# J4-B64_B65.net
KiCad netlist of a schematic drawn in Altium Designer
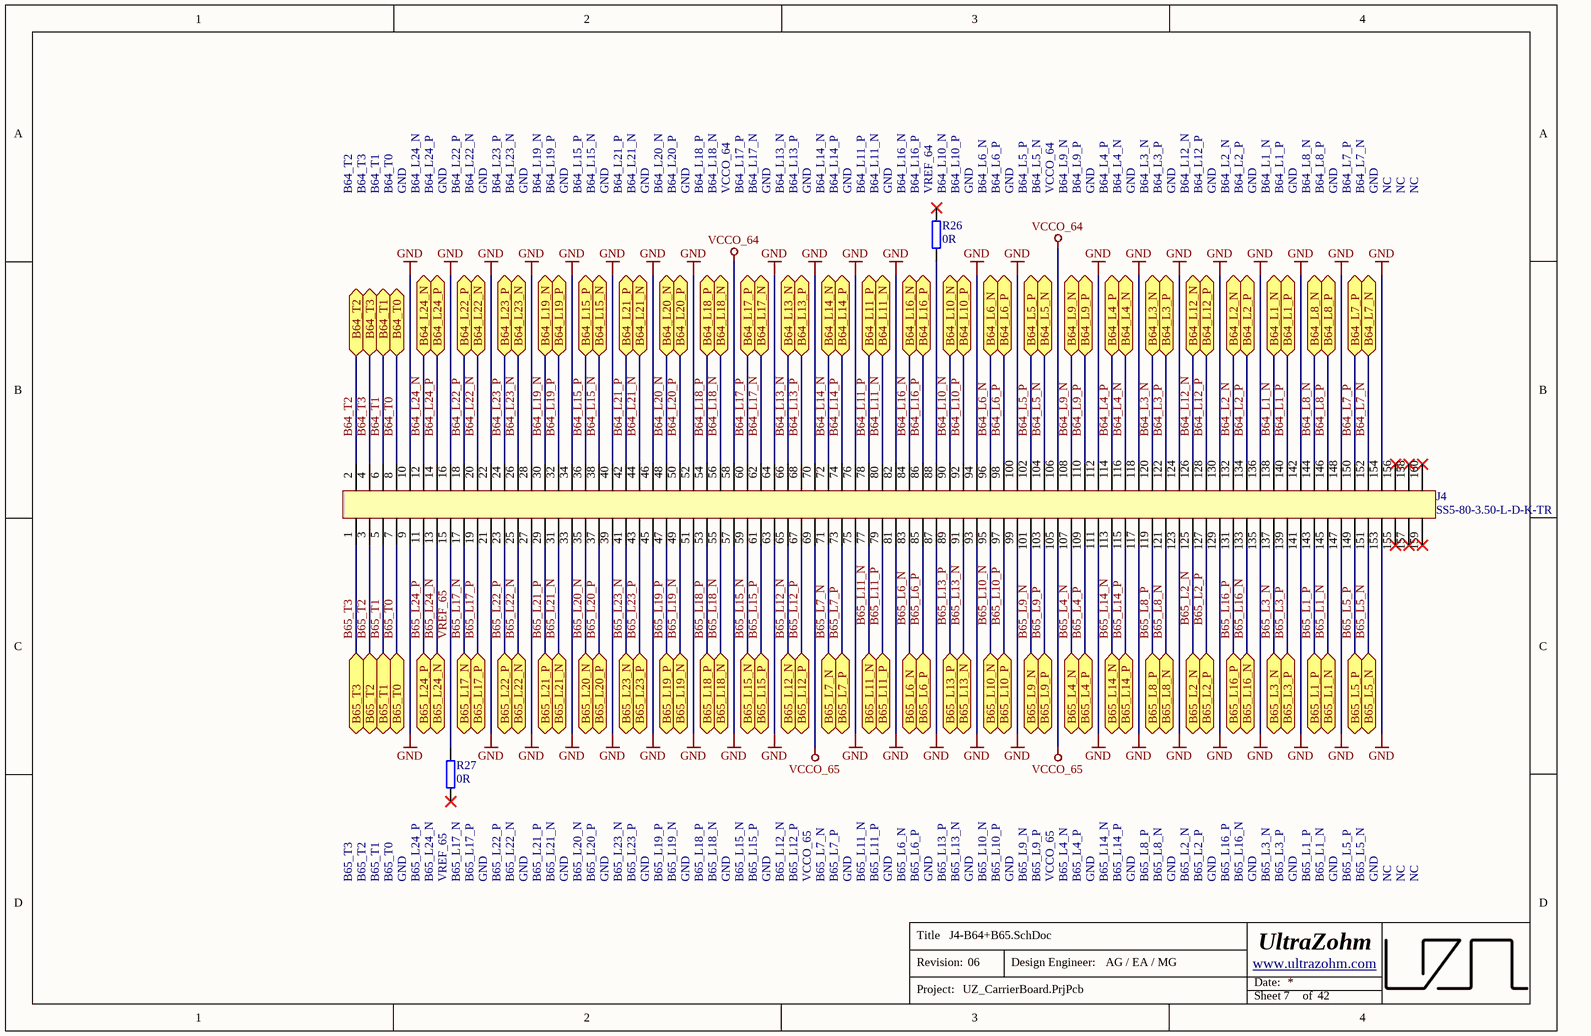
[diagram p0: J4-B64+B65.SchDoc]

(export (version "E")
  (design (tool "Eeschema 10.0.6"))
  (components
    (comp (ref "J4")
      (value "SS5-80-3.50-L-D-K-TR")
      (footprint "SS5-80-3.50-L-D-K-TR")
      (description "0.5 mm Ultra Fine Pitch Socket REF192552-01, 160 Pins")
      (fields
        (field (name "MANUFACTURER") "SAMTEC")
        (field (name "LCSC PART NUMBER") "C5292077")
        (field (name "CREATED FROM") "MGremer")
      )
      (libsource (lib "user") (part "SS5-80-3.50-L-D-K-TR"))
    )
    (comp (ref "R26")
      (value "0R")
      (footprint "R_0603_TE")
      (description "Generic resistor")
      (fields
        (field (name "TOLERANCE") "1 %")
        (field (name "MANUFACTURER PART NUMBER") "UZgen_R_0603_0R")
        (field (name "CREATED FROM") "UZgenTool")
      )
      (libsource (lib "user") (part "RES"))
    )
    (comp (ref "R27")
      (value "0R")
      (footprint "R_0603_TE")
      (description "Generic resistor")
      (fields
        (field (name "TOLERANCE") "1 %")
        (field (name "MANUFACTURER PART NUMBER") "UZgen_R_0603_0R")
        (field (name "CREATED FROM") "UZgenTool")
      )
      (libsource (lib "user") (part "RES"))
    )
  )
  (nets
    (net (code "1") (name "/B64_L1_N") (class "Default")
      (node (ref "J4") (pin "138") (pinfunction "138_138") (pintype "passive"))
    )
    (net (code "2") (name "/B64_L1_P") (class "Default")
      (node (ref "J4") (pin "140") (pinfunction "140_140") (pintype "passive"))
    )
    (net (code "3") (name "/B64_L2_N") (class "Default")
      (node (ref "J4") (pin "132") (pinfunction "132_132") (pintype "passive"))
    )
    (net (code "4") (name "/B64_L2_P") (class "Default")
      (node (ref "J4") (pin "134") (pinfunction "134_134") (pintype "passive"))
    )
    (net (code "5") (name "/B64_L3_N") (class "Default")
      (node (ref "J4") (pin "120") (pinfunction "120_120") (pintype "passive"))
    )
    (net (code "6") (name "/B64_L3_P") (class "Default")
      (node (ref "J4") (pin "122") (pinfunction "122_122") (pintype "passive"))
    )
    (net (code "7") (name "/B64_L4_N") (class "Default")
      (node (ref "J4") (pin "116") (pinfunction "116_116") (pintype "passive"))
    )
    (net (code "8") (name "/B64_L4_P") (class "Default")
      (node (ref "J4") (pin "114") (pinfunction "114_114") (pintype "passive"))
    )
    (net (code "9") (name "/B64_L5_N") (class "Default")
      (node (ref "J4") (pin "104") (pinfunction "104_104") (pintype "passive"))
    )
    (net (code "10") (name "/B64_L5_P") (class "Default")
      (node (ref "J4") (pin "102") (pinfunction "102_102") (pintype "passive"))
    )
    (net (code "11") (name "/B64_L6_N") (class "Default")
      (node (ref "J4") (pin "96") (pinfunction "96_96") (pintype "passive"))
    )
    (net (code "12") (name "/B64_L6_P") (class "Default")
      (node (ref "J4") (pin "98") (pinfunction "98_98") (pintype "passive"))
    )
    (net (code "13") (name "/B64_L7_N") (class "Default")
      (node (ref "J4") (pin "152") (pinfunction "152_152") (pintype "passive"))
    )
    (net (code "14") (name "/B64_L7_P") (class "Default")
      (node (ref "J4") (pin "150") (pinfunction "150_150") (pintype "passive"))
    )
    (net (code "15") (name "/B64_L8_N") (class "Default")
      (node (ref "J4") (pin "144") (pinfunction "144_144") (pintype "passive"))
    )
    (net (code "16") (name "/B64_L8_P") (class "Default")
      (node (ref "J4") (pin "146") (pinfunction "146_146") (pintype "passive"))
    )
    (net (code "17") (name "/B64_L9_N") (class "Default")
      (node (ref "J4") (pin "108") (pinfunction "108_108") (pintype "passive"))
    )
    (net (code "18") (name "/B64_L9_P") (class "Default")
      (node (ref "J4") (pin "110") (pinfunction "110_110") (pintype "passive"))
    )
    (net (code "19") (name "/B64_L10_N") (class "Default")
      (node (ref "J4") (pin "90") (pinfunction "90_90") (pintype "passive"))
    )
    (net (code "20") (name "/B64_L10_P") (class "Default")
      (node (ref "J4") (pin "92") (pinfunction "92_92") (pintype "passive"))
    )
    (net (code "21") (name "/B64_L11_N") (class "Default")
      (node (ref "J4") (pin "80") (pinfunction "80_80") (pintype "passive"))
    )
    (net (code "22") (name "/B64_L11_P") (class "Default")
      (node (ref "J4") (pin "78") (pinfunction "78_78") (pintype "passive"))
    )
    (net (code "23") (name "/B64_L12_N") (class "Default")
      (node (ref "J4") (pin "126") (pinfunction "126_126") (pintype "passive"))
    )
    (net (code "24") (name "/B64_L12_P") (class "Default")
      (node (ref "J4") (pin "128") (pinfunction "128_128") (pintype "passive"))
    )
    (net (code "25") (name "/B64_L13_N") (class "Default")
      (node (ref "J4") (pin "66") (pinfunction "66_66") (pintype "passive"))
    )
    (net (code "26") (name "/B64_L13_P") (class "Default")
      (node (ref "J4") (pin "68") (pinfunction "68_68") (pintype "passive"))
    )
    (net (code "27") (name "/B64_L14_N") (class "Default")
      (node (ref "J4") (pin "72") (pinfunction "72_72") (pintype "passive"))
    )
    (net (code "28") (name "/B64_L14_P") (class "Default")
      (node (ref "J4") (pin "74") (pinfunction "74_74") (pintype "passive"))
    )
    (net (code "29") (name "/B64_L15_N") (class "Default")
      (node (ref "J4") (pin "38") (pinfunction "38_38") (pintype "passive"))
    )
    (net (code "30") (name "/B64_L15_P") (class "Default")
      (node (ref "J4") (pin "36") (pinfunction "36_36") (pintype "passive"))
    )
    (net (code "31") (name "/B64_L16_N") (class "Default")
      (node (ref "J4") (pin "84") (pinfunction "84_84") (pintype "passive"))
    )
    (net (code "32") (name "/B64_L16_P") (class "Default")
      (node (ref "J4") (pin "86") (pinfunction "86_86") (pintype "passive"))
    )
    (net (code "33") (name "/B64_L17_N") (class "Default")
      (node (ref "J4") (pin "62") (pinfunction "62_62") (pintype "passive"))
    )
    (net (code "34") (name "/B64_L17_P") (class "Default")
      (node (ref "J4") (pin "60") (pinfunction "60_60") (pintype "passive"))
    )
    (net (code "35") (name "/B64_L18_N") (class "Default")
      (node (ref "J4") (pin "56") (pinfunction "56_56") (pintype "passive"))
    )
    (net (code "36") (name "/B64_L18_P") (class "Default")
      (node (ref "J4") (pin "54") (pinfunction "54_54") (pintype "passive"))
    )
    (net (code "37") (name "/B64_L19_N") (class "Default")
      (node (ref "J4") (pin "30") (pinfunction "30_30") (pintype "passive"))
    )
    (net (code "38") (name "/B64_L19_P") (class "Default")
      (node (ref "J4") (pin "32") (pinfunction "32_32") (pintype "passive"))
    )
    (net (code "39") (name "/B64_L20_N") (class "Default")
      (node (ref "J4") (pin "48") (pinfunction "48_48") (pintype "passive"))
    )
    (net (code "40") (name "/B64_L20_P") (class "Default")
      (node (ref "J4") (pin "50") (pinfunction "50_50") (pintype "passive"))
    )
    (net (code "41") (name "/B64_L21_N") (class "Default")
      (node (ref "J4") (pin "44") (pinfunction "44_44") (pintype "passive"))
    )
    (net (code "42") (name "/B64_L21_P") (class "Default")
      (node (ref "J4") (pin "42") (pinfunction "42_42") (pintype "passive"))
    )
    (net (code "43") (name "/B64_L22_N") (class "Default")
      (node (ref "J4") (pin "20") (pinfunction "20_20") (pintype "passive"))
    )
    (net (code "44") (name "/B64_L22_P") (class "Default")
      (node (ref "J4") (pin "18") (pinfunction "18_18") (pintype "passive"))
    )
    (net (code "45") (name "/B64_L23_N") (class "Default")
      (node (ref "J4") (pin "26") (pinfunction "26_26") (pintype "passive"))
    )
    (net (code "46") (name "/B64_L23_P") (class "Default")
      (node (ref "J4") (pin "24") (pinfunction "24_24") (pintype "passive"))
    )
    (net (code "47") (name "/B64_L24_N") (class "Default")
      (node (ref "J4") (pin "12") (pinfunction "12_12") (pintype "passive"))
    )
    (net (code "48") (name "/B64_L24_P") (class "Default")
      (node (ref "J4") (pin "14") (pinfunction "14_14") (pintype "passive"))
    )
    (net (code "49") (name "/B64_T0") (class "Default")
      (node (ref "J4") (pin "8") (pinfunction "8_8") (pintype "passive"))
    )
    (net (code "50") (name "/B64_T1") (class "Default")
      (node (ref "J4") (pin "6") (pinfunction "6_6") (pintype "passive"))
    )
    (net (code "51") (name "/B64_T2") (class "Default")
      (node (ref "J4") (pin "2") (pinfunction "2_2") (pintype "passive"))
    )
    (net (code "52") (name "/B64_T3") (class "Default")
      (node (ref "J4") (pin "4") (pinfunction "4_4") (pintype "passive"))
    )
    (net (code "53") (name "/B65_L1_N") (class "Default")
      (node (ref "J4") (pin "145") (pinfunction "145_145") (pintype "passive"))
    )
    (net (code "54") (name "/B65_L1_P") (class "Default")
      (node (ref "J4") (pin "143") (pinfunction "143_143") (pintype "passive"))
    )
    (net (code "55") (name "/B65_L2_N") (class "Default")
      (node (ref "J4") (pin "125") (pinfunction "125_125") (pintype "passive"))
    )
    (net (code "56") (name "/B65_L2_P") (class "Default")
      (node (ref "J4") (pin "127") (pinfunction "127_127") (pintype "passive"))
    )
    (net (code "57") (name "/B65_L3_N") (class "Default")
      (node (ref "J4") (pin "137") (pinfunction "137_137") (pintype "passive"))
    )
    (net (code "58") (name "/B65_L3_P") (class "Default")
      (node (ref "J4") (pin "139") (pinfunction "139_139") (pintype "passive"))
    )
    (net (code "59") (name "/B65_L4_N") (class "Default")
      (node (ref "J4") (pin "107") (pinfunction "107_107") (pintype "passive"))
    )
    (net (code "60") (name "/B65_L4_P") (class "Default")
      (node (ref "J4") (pin "109") (pinfunction "109_109") (pintype "passive"))
    )
    (net (code "61") (name "/B65_L5_N") (class "Default")
      (node (ref "J4") (pin "151") (pinfunction "151_151") (pintype "passive"))
    )
    (net (code "62") (name "/B65_L5_P") (class "Default")
      (node (ref "J4") (pin "149") (pinfunction "149_149") (pintype "passive"))
    )
    (net (code "63") (name "/B65_L6_N") (class "Default")
      (node (ref "J4") (pin "83") (pinfunction "83_83") (pintype "passive"))
    )
    (net (code "64") (name "/B65_L6_P") (class "Default")
      (node (ref "J4") (pin "85") (pinfunction "85_85") (pintype "passive"))
    )
    (net (code "65") (name "/B65_L7_N") (class "Default")
      (node (ref "J4") (pin "71") (pinfunction "71_71") (pintype "passive"))
    )
    (net (code "66") (name "/B65_L7_P") (class "Default")
      (node (ref "J4") (pin "73") (pinfunction "73_73") (pintype "passive"))
    )
    (net (code "67") (name "/B65_L8_N") (class "Default")
      (node (ref "J4") (pin "121") (pinfunction "121_121") (pintype "passive"))
    )
    (net (code "68") (name "/B65_L8_P") (class "Default")
      (node (ref "J4") (pin "119") (pinfunction "119_119") (pintype "passive"))
    )
    (net (code "69") (name "/B65_L9_N") (class "Default")
      (node (ref "J4") (pin "101") (pinfunction "101_101") (pintype "passive"))
    )
    (net (code "70") (name "/B65_L9_P") (class "Default")
      (node (ref "J4") (pin "103") (pinfunction "103_103") (pintype "passive"))
    )
    (net (code "71") (name "/B65_L10_N") (class "Default")
      (node (ref "J4") (pin "95") (pinfunction "95_95") (pintype "passive"))
    )
    (net (code "72") (name "/B65_L10_P") (class "Default")
      (node (ref "J4") (pin "97") (pinfunction "97_97") (pintype "passive"))
    )
    (net (code "73") (name "/B65_L11_N") (class "Default")
      (node (ref "J4") (pin "77") (pinfunction "77_77") (pintype "passive"))
    )
    (net (code "74") (name "/B65_L11_P") (class "Default")
      (node (ref "J4") (pin "79") (pinfunction "79_79") (pintype "passive"))
    )
    (net (code "75") (name "/B65_L12_N") (class "Default")
      (node (ref "J4") (pin "65") (pinfunction "65_65") (pintype "passive"))
    )
    (net (code "76") (name "/B65_L12_P") (class "Default")
      (node (ref "J4") (pin "67") (pinfunction "67_67") (pintype "passive"))
    )
    (net (code "77") (name "/B65_L13_N") (class "Default")
      (node (ref "J4") (pin "91") (pinfunction "91_91") (pintype "passive"))
    )
    (net (code "78") (name "/B65_L13_P") (class "Default")
      (node (ref "J4") (pin "89") (pinfunction "89_89") (pintype "passive"))
    )
    (net (code "79") (name "/B65_L14_N") (class "Default")
      (node (ref "J4") (pin "113") (pinfunction "113_113") (pintype "passive"))
    )
    (net (code "80") (name "/B65_L14_P") (class "Default")
      (node (ref "J4") (pin "115") (pinfunction "115_115") (pintype "passive"))
    )
    (net (code "81") (name "/B65_L15_N") (class "Default")
      (node (ref "J4") (pin "59") (pinfunction "59_59") (pintype "passive"))
    )
    (net (code "82") (name "/B65_L15_P") (class "Default")
      (node (ref "J4") (pin "61") (pinfunction "61_61") (pintype "passive"))
    )
    (net (code "83") (name "/B65_L16_N") (class "Default")
      (node (ref "J4") (pin "133") (pinfunction "133_133") (pintype "passive"))
    )
    (net (code "84") (name "/B65_L16_P") (class "Default")
      (node (ref "J4") (pin "131") (pinfunction "131_131") (pintype "passive"))
    )
    (net (code "85") (name "/B65_L17_N") (class "Default")
      (node (ref "J4") (pin "17") (pinfunction "17_17") (pintype "passive"))
    )
    (net (code "86") (name "/B65_L17_P") (class "Default")
      (node (ref "J4") (pin "19") (pinfunction "19_19") (pintype "passive"))
    )
    (net (code "87") (name "/B65_L18_N") (class "Default")
      (node (ref "J4") (pin "55") (pinfunction "55_55") (pintype "passive"))
    )
    (net (code "88") (name "/B65_L18_P") (class "Default")
      (node (ref "J4") (pin "53") (pinfunction "53_53") (pintype "passive"))
    )
    (net (code "89") (name "/B65_L19_N") (class "Default")
      (node (ref "J4") (pin "49") (pinfunction "49_49") (pintype "passive"))
    )
    (net (code "90") (name "/B65_L19_P") (class "Default")
      (node (ref "J4") (pin "47") (pinfunction "47_47") (pintype "passive"))
    )
    (net (code "91") (name "/B65_L20_N") (class "Default")
      (node (ref "J4") (pin "35") (pinfunction "35_35") (pintype "passive"))
    )
    (net (code "92") (name "/B65_L20_P") (class "Default")
      (node (ref "J4") (pin "37") (pinfunction "37_37") (pintype "passive"))
    )
    (net (code "93") (name "/B65_L21_N") (class "Default")
      (node (ref "J4") (pin "31") (pinfunction "31_31") (pintype "passive"))
    )
    (net (code "94") (name "/B65_L21_P") (class "Default")
      (node (ref "J4") (pin "29") (pinfunction "29_29") (pintype "passive"))
    )
    (net (code "95") (name "/B65_L22_N") (class "Default")
      (node (ref "J4") (pin "25") (pinfunction "25_25") (pintype "passive"))
    )
    (net (code "96") (name "/B65_L22_P") (class "Default")
      (node (ref "J4") (pin "23") (pinfunction "23_23") (pintype "passive"))
    )
    (net (code "97") (name "/B65_L23_N") (class "Default")
      (node (ref "J4") (pin "41") (pinfunction "41_41") (pintype "passive"))
    )
    (net (code "98") (name "/B65_L23_P") (class "Default")
      (node (ref "J4") (pin "43") (pinfunction "43_43") (pintype "passive"))
    )
    (net (code "99") (name "/B65_L24_N") (class "Default")
      (node (ref "J4") (pin "13") (pinfunction "13_13") (pintype "passive"))
    )
    (net (code "100") (name "/B65_L24_P") (class "Default")
      (node (ref "J4") (pin "11") (pinfunction "11_11") (pintype "passive"))
    )
    (net (code "101") (name "/B65_T0") (class "Default")
      (node (ref "J4") (pin "7") (pinfunction "7_7") (pintype "passive"))
    )
    (net (code "102") (name "/B65_T1") (class "Default")
      (node (ref "J4") (pin "5") (pinfunction "5_5") (pintype "passive"))
    )
    (net (code "103") (name "/B65_T2") (class "Default")
      (node (ref "J4") (pin "3") (pinfunction "3_3") (pintype "passive"))
    )
    (net (code "104") (name "/B65_T3") (class "Default")
      (node (ref "J4") (pin "1") (pinfunction "1_1") (pintype "passive"))
    )
    (net (code "105") (name "/VREF_65") (class "Default")
      (node (ref "J4") (pin "15") (pinfunction "15_15") (pintype "passive"))
      (node (ref "R27") (pin "2") (pinfunction "2_2") (pintype "passive"))
    )
    (net (code "106") (name "GND") (class "Default")
      (node (ref "J4") (pin "10") (pinfunction "10_10") (pintype "passive"))
      (node (ref "J4") (pin "100") (pinfunction "100_100") (pintype "passive"))
      (node (ref "J4") (pin "111") (pinfunction "111_111") (pintype "passive"))
      (node (ref "J4") (pin "112") (pinfunction "112_112") (pintype "passive"))
      (node (ref "J4") (pin "117") (pinfunction "117_117") (pintype "passive"))
      (node (ref "J4") (pin "118") (pinfunction "118_118") (pintype "passive"))
      (node (ref "J4") (pin "123") (pinfunction "123_123") (pintype "passive"))
      (node (ref "J4") (pin "124") (pinfunction "124_124") (pintype "passive"))
      (node (ref "J4") (pin "129") (pinfunction "129_129") (pintype "passive"))
      (node (ref "J4") (pin "130") (pinfunction "130_130") (pintype "passive"))
      (node (ref "J4") (pin "135") (pinfunction "135_135") (pintype "passive"))
      (node (ref "J4") (pin "136") (pinfunction "136_136") (pintype "passive"))
      (node (ref "J4") (pin "141") (pinfunction "141_141") (pintype "passive"))
      (node (ref "J4") (pin "142") (pinfunction "142_142") (pintype "passive"))
      (node (ref "J4") (pin "147") (pinfunction "147_147") (pintype "passive"))
      (node (ref "J4") (pin "148") (pinfunction "148_148") (pintype "passive"))
      (node (ref "J4") (pin "153") (pinfunction "153_153") (pintype "passive"))
      (node (ref "J4") (pin "154") (pinfunction "154_154") (pintype "passive"))
      (node (ref "J4") (pin "16") (pinfunction "16_16") (pintype "passive"))
      (node (ref "J4") (pin "21") (pinfunction "21_21") (pintype "passive"))
      (node (ref "J4") (pin "22") (pinfunction "22_22") (pintype "passive"))
      (node (ref "J4") (pin "27") (pinfunction "27_27") (pintype "passive"))
      (node (ref "J4") (pin "28") (pinfunction "28_28") (pintype "passive"))
      (node (ref "J4") (pin "33") (pinfunction "33_33") (pintype "passive"))
      (node (ref "J4") (pin "34") (pinfunction "34_34") (pintype "passive"))
      (node (ref "J4") (pin "39") (pinfunction "39_39") (pintype "passive"))
      (node (ref "J4") (pin "40") (pinfunction "40_40") (pintype "passive"))
      (node (ref "J4") (pin "45") (pinfunction "45_45") (pintype "passive"))
      (node (ref "J4") (pin "46") (pinfunction "46_46") (pintype "passive"))
      (node (ref "J4") (pin "51") (pinfunction "51_51") (pintype "passive"))
      (node (ref "J4") (pin "52") (pinfunction "52_52") (pintype "passive"))
      (node (ref "J4") (pin "57") (pinfunction "57_57") (pintype "passive"))
      (node (ref "J4") (pin "63") (pinfunction "63_63") (pintype "passive"))
      (node (ref "J4") (pin "64") (pinfunction "64_64") (pintype "passive"))
      (node (ref "J4") (pin "70") (pinfunction "70_70") (pintype "passive"))
      (node (ref "J4") (pin "75") (pinfunction "75_75") (pintype "passive"))
      (node (ref "J4") (pin "76") (pinfunction "76_76") (pintype "passive"))
      (node (ref "J4") (pin "81") (pinfunction "81_81") (pintype "passive"))
      (node (ref "J4") (pin "82") (pinfunction "82_82") (pintype "passive"))
      (node (ref "J4") (pin "87") (pinfunction "87_87") (pintype "passive"))
      (node (ref "J4") (pin "9") (pinfunction "9_9") (pintype "passive"))
      (node (ref "J4") (pin "93") (pinfunction "93_93") (pintype "passive"))
      (node (ref "J4") (pin "94") (pinfunction "94_94") (pintype "passive"))
      (node (ref "J4") (pin "99") (pinfunction "99_99") (pintype "passive"))
    )
    (net (code "107") (name "Net-(J4-Pad88)") (class "Default")
      (node (ref "J4") (pin "88") (pinfunction "88_88") (pintype "passive"))
      (node (ref "R26") (pin "1") (pinfunction "1_1") (pintype "passive"))
    )
    (net (code "108") (name "VCCO_64") (class "Default")
      (node (ref "J4") (pin "106") (pinfunction "106_106") (pintype "passive"))
      (node (ref "J4") (pin "58") (pinfunction "58_58") (pintype "passive"))
    )
    (net (code "109") (name "VCCO_65") (class "Default")
      (node (ref "J4") (pin "105") (pinfunction "105_105") (pintype "passive"))
      (node (ref "J4") (pin "69") (pinfunction "69_69") (pintype "passive"))
    )
    (net (code "110") (name "unconnected-(J4-Pad155)") (class "Default")
      (node (ref "J4") (pin "155") (pinfunction "155_155") (pintype "passive+no_connect"))
    )
    (net (code "111") (name "unconnected-(J4-Pad156)") (class "Default")
      (node (ref "J4") (pin "156") (pinfunction "156_156") (pintype "passive+no_connect"))
    )
    (net (code "112") (name "unconnected-(J4-Pad157)") (class "Default")
      (node (ref "J4") (pin "157") (pinfunction "157_157") (pintype "passive+no_connect"))
    )
    (net (code "113") (name "unconnected-(J4-Pad158)") (class "Default")
      (node (ref "J4") (pin "158") (pinfunction "158_158") (pintype "passive+no_connect"))
    )
    (net (code "114") (name "unconnected-(J4-Pad159)") (class "Default")
      (node (ref "J4") (pin "159") (pinfunction "159_159") (pintype "passive+no_connect"))
    )
    (net (code "115") (name "unconnected-(J4-Pad160)") (class "Default")
      (node (ref "J4") (pin "160") (pinfunction "160_160") (pintype "passive+no_connect"))
    )
    (net (code "116") (name "unconnected-(R26-Pad2)") (class "Default")
      (node (ref "R26") (pin "2") (pinfunction "2_2") (pintype "passive+no_connect"))
    )
    (net (code "117") (name "unconnected-(R27-Pad1)") (class "Default")
      (node (ref "R27") (pin "1") (pinfunction "1_1") (pintype "passive+no_connect"))
    )
  )
)
